# power.net
KiCad netlist of a schematic drawn in Altium Designer
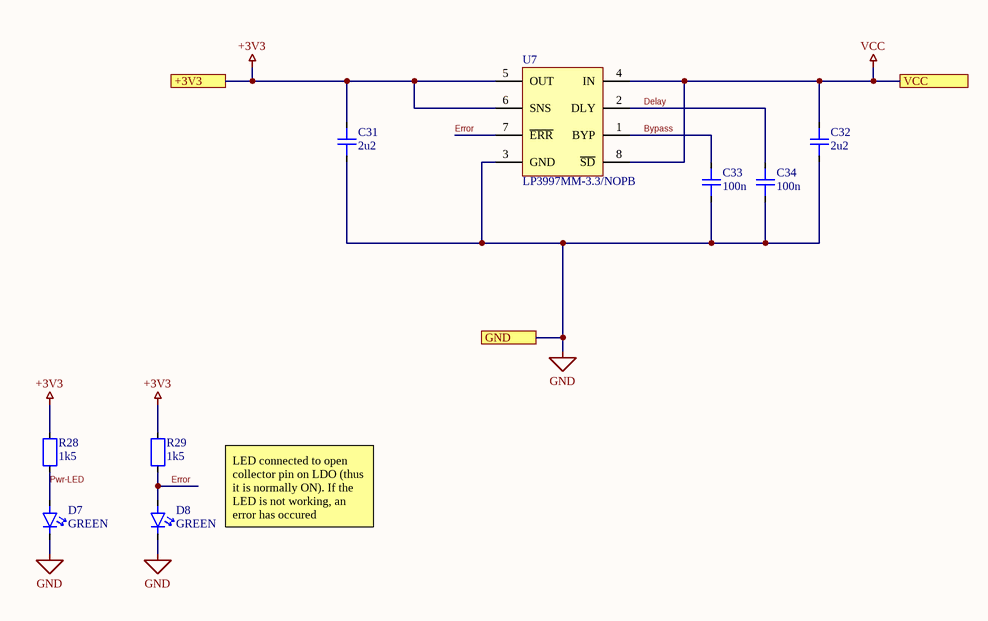
[diagram p0: power.SchDoc]

(export (version "E")
  (design (tool "Eeschema 10.0.6"))
  (components
    (comp (ref "C31")
      (value "2u2")
      (footprint "CAP0603")
      (libsource (lib "Integrated_Library_main") (part "Capacitor"))
    )
    (comp (ref "C32")
      (value "2u2")
      (footprint "CAP0603")
      (libsource (lib "Integrated_Library_main") (part "Capacitor"))
    )
    (comp (ref "C33")
      (value "100n")
      (footprint "CAP0603")
      (libsource (lib "Integrated_Library_main") (part "Capacitor"))
    )
    (comp (ref "C34")
      (value "100n")
      (footprint "CAP0603")
      (libsource (lib "Integrated_Library_main") (part "Capacitor"))
    )
    (comp (ref "D7")
      (value "GREEN")
      (footprint "LED0603")
      (libsource (lib "Integrated_Library_main") (part "LED"))
    )
    (comp (ref "D8")
      (value "GREEN")
      (footprint "LED0603")
      (libsource (lib "Integrated_Library_main") (part "LED"))
    )
    (comp (ref "R28")
      (value "1k5")
      (footprint "RES0603")
      (libsource (lib "Integrated_Library_main") (part "Resistor"))
    )
    (comp (ref "R29")
      (value "1k5")
      (footprint "RES0603")
      (libsource (lib "Integrated_Library_main") (part "Resistor"))
    )
    (comp (ref "U7")
      (value "LP3997MM-3.3/NOPB")
      (footprint "DGK0008A_N")
      (description "Micropower 250mA CMOS LDO Regulator with Error Flag / Power-On-Reset, 8-pin Mini SOIC, Pb-Free")
      (fields (field (name "MANUFACTURER") "Texas Instruments"))
      (libsource (lib "Integrated_Library_main") (part "LP3997MM-3.3/NOPB"))
    )
  )
  (nets
    (net (code "1") (name "+3V3") (class "Default")
      (node (ref "C31") (pin "1") (pintype "passive"))
      (node (ref "R28") (pin "1") (pintype "passive"))
      (node (ref "R29") (pin "1") (pintype "passive"))
      (node (ref "U7") (pin "5") (pinfunction "OUT_5") (pintype "power_in"))
      (node (ref "U7") (pin "6") (pinfunction "SNS_6") (pintype "passive"))
    )
    (net (code "2") (name "/Bypass") (class "Default")
      (node (ref "C33") (pin "1") (pintype "passive"))
      (node (ref "U7") (pin "1") (pinfunction "BYP_1") (pintype "passive"))
    )
    (net (code "3") (name "/Delay") (class "Default")
      (node (ref "C34") (pin "1") (pintype "passive"))
      (node (ref "U7") (pin "2") (pinfunction "DLY_2") (pintype "passive"))
    )
    (net (code "4") (name "/Error") (class "Default")
      (node (ref "D8") (pin "1") (pintype "passive"))
      (node (ref "R29") (pin "2") (pintype "passive"))
      (node (ref "U7") (pin "7") (pinfunction "~{ERR}_7") (pintype "open_collector"))
    )
    (net (code "5") (name "/Pwr-LED") (class "Default")
      (node (ref "D7") (pin "1") (pintype "passive"))
      (node (ref "R28") (pin "2") (pintype "passive"))
    )
    (net (code "6") (name "GND") (class "Default")
      (node (ref "C31") (pin "2") (pintype "passive"))
      (node (ref "C32") (pin "2") (pintype "passive"))
      (node (ref "C33") (pin "2") (pintype "passive"))
      (node (ref "C34") (pin "2") (pintype "passive"))
      (node (ref "D7") (pin "2") (pintype "passive"))
      (node (ref "D8") (pin "2") (pintype "passive"))
      (node (ref "U7") (pin "3") (pinfunction "GND_3") (pintype "power_in"))
    )
    (net (code "7") (name "VCC") (class "Default")
      (node (ref "C32") (pin "1") (pintype "passive"))
      (node (ref "U7") (pin "4") (pinfunction "IN_4") (pintype "power_in"))
      (node (ref "U7") (pin "8") (pinfunction "~{SD}_8") (pintype "passive"))
    )
  )
)
